# SCH_Elektrisch_Schema_B_2022-11-22.net
KiCad netlist of a schematic drawn in EasyEDA
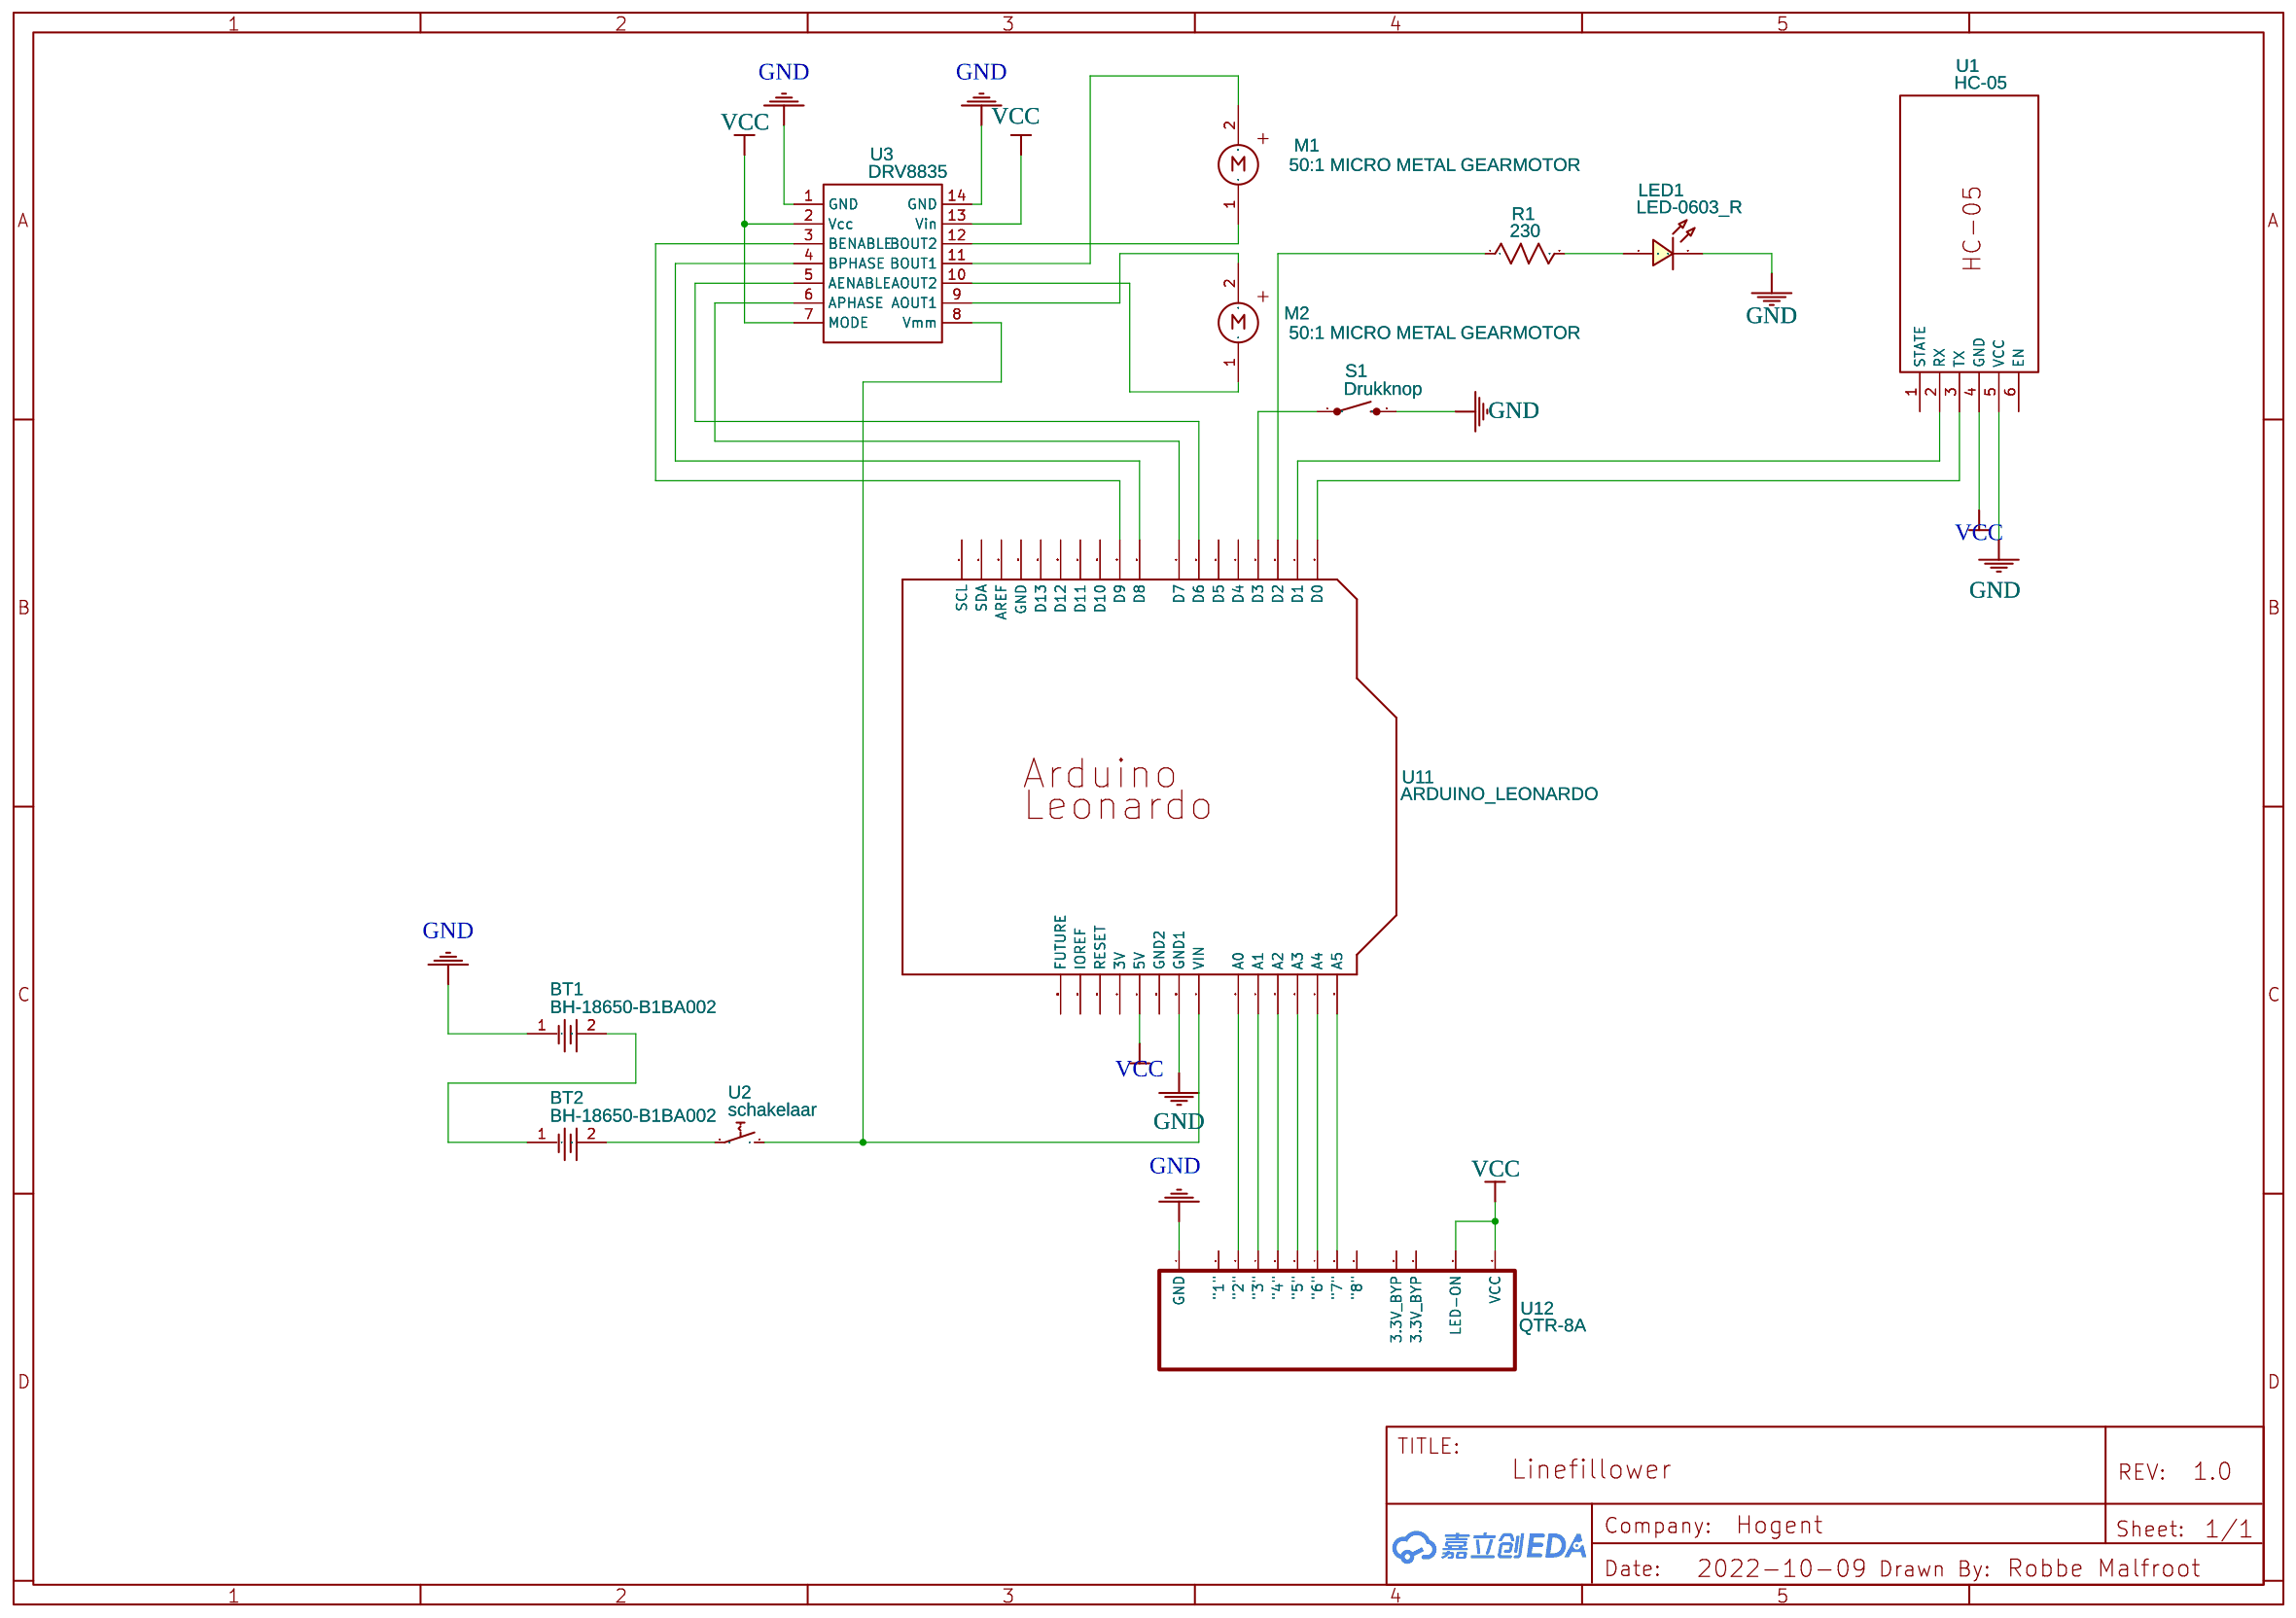
[diagram p0: Elektrisch schema B]
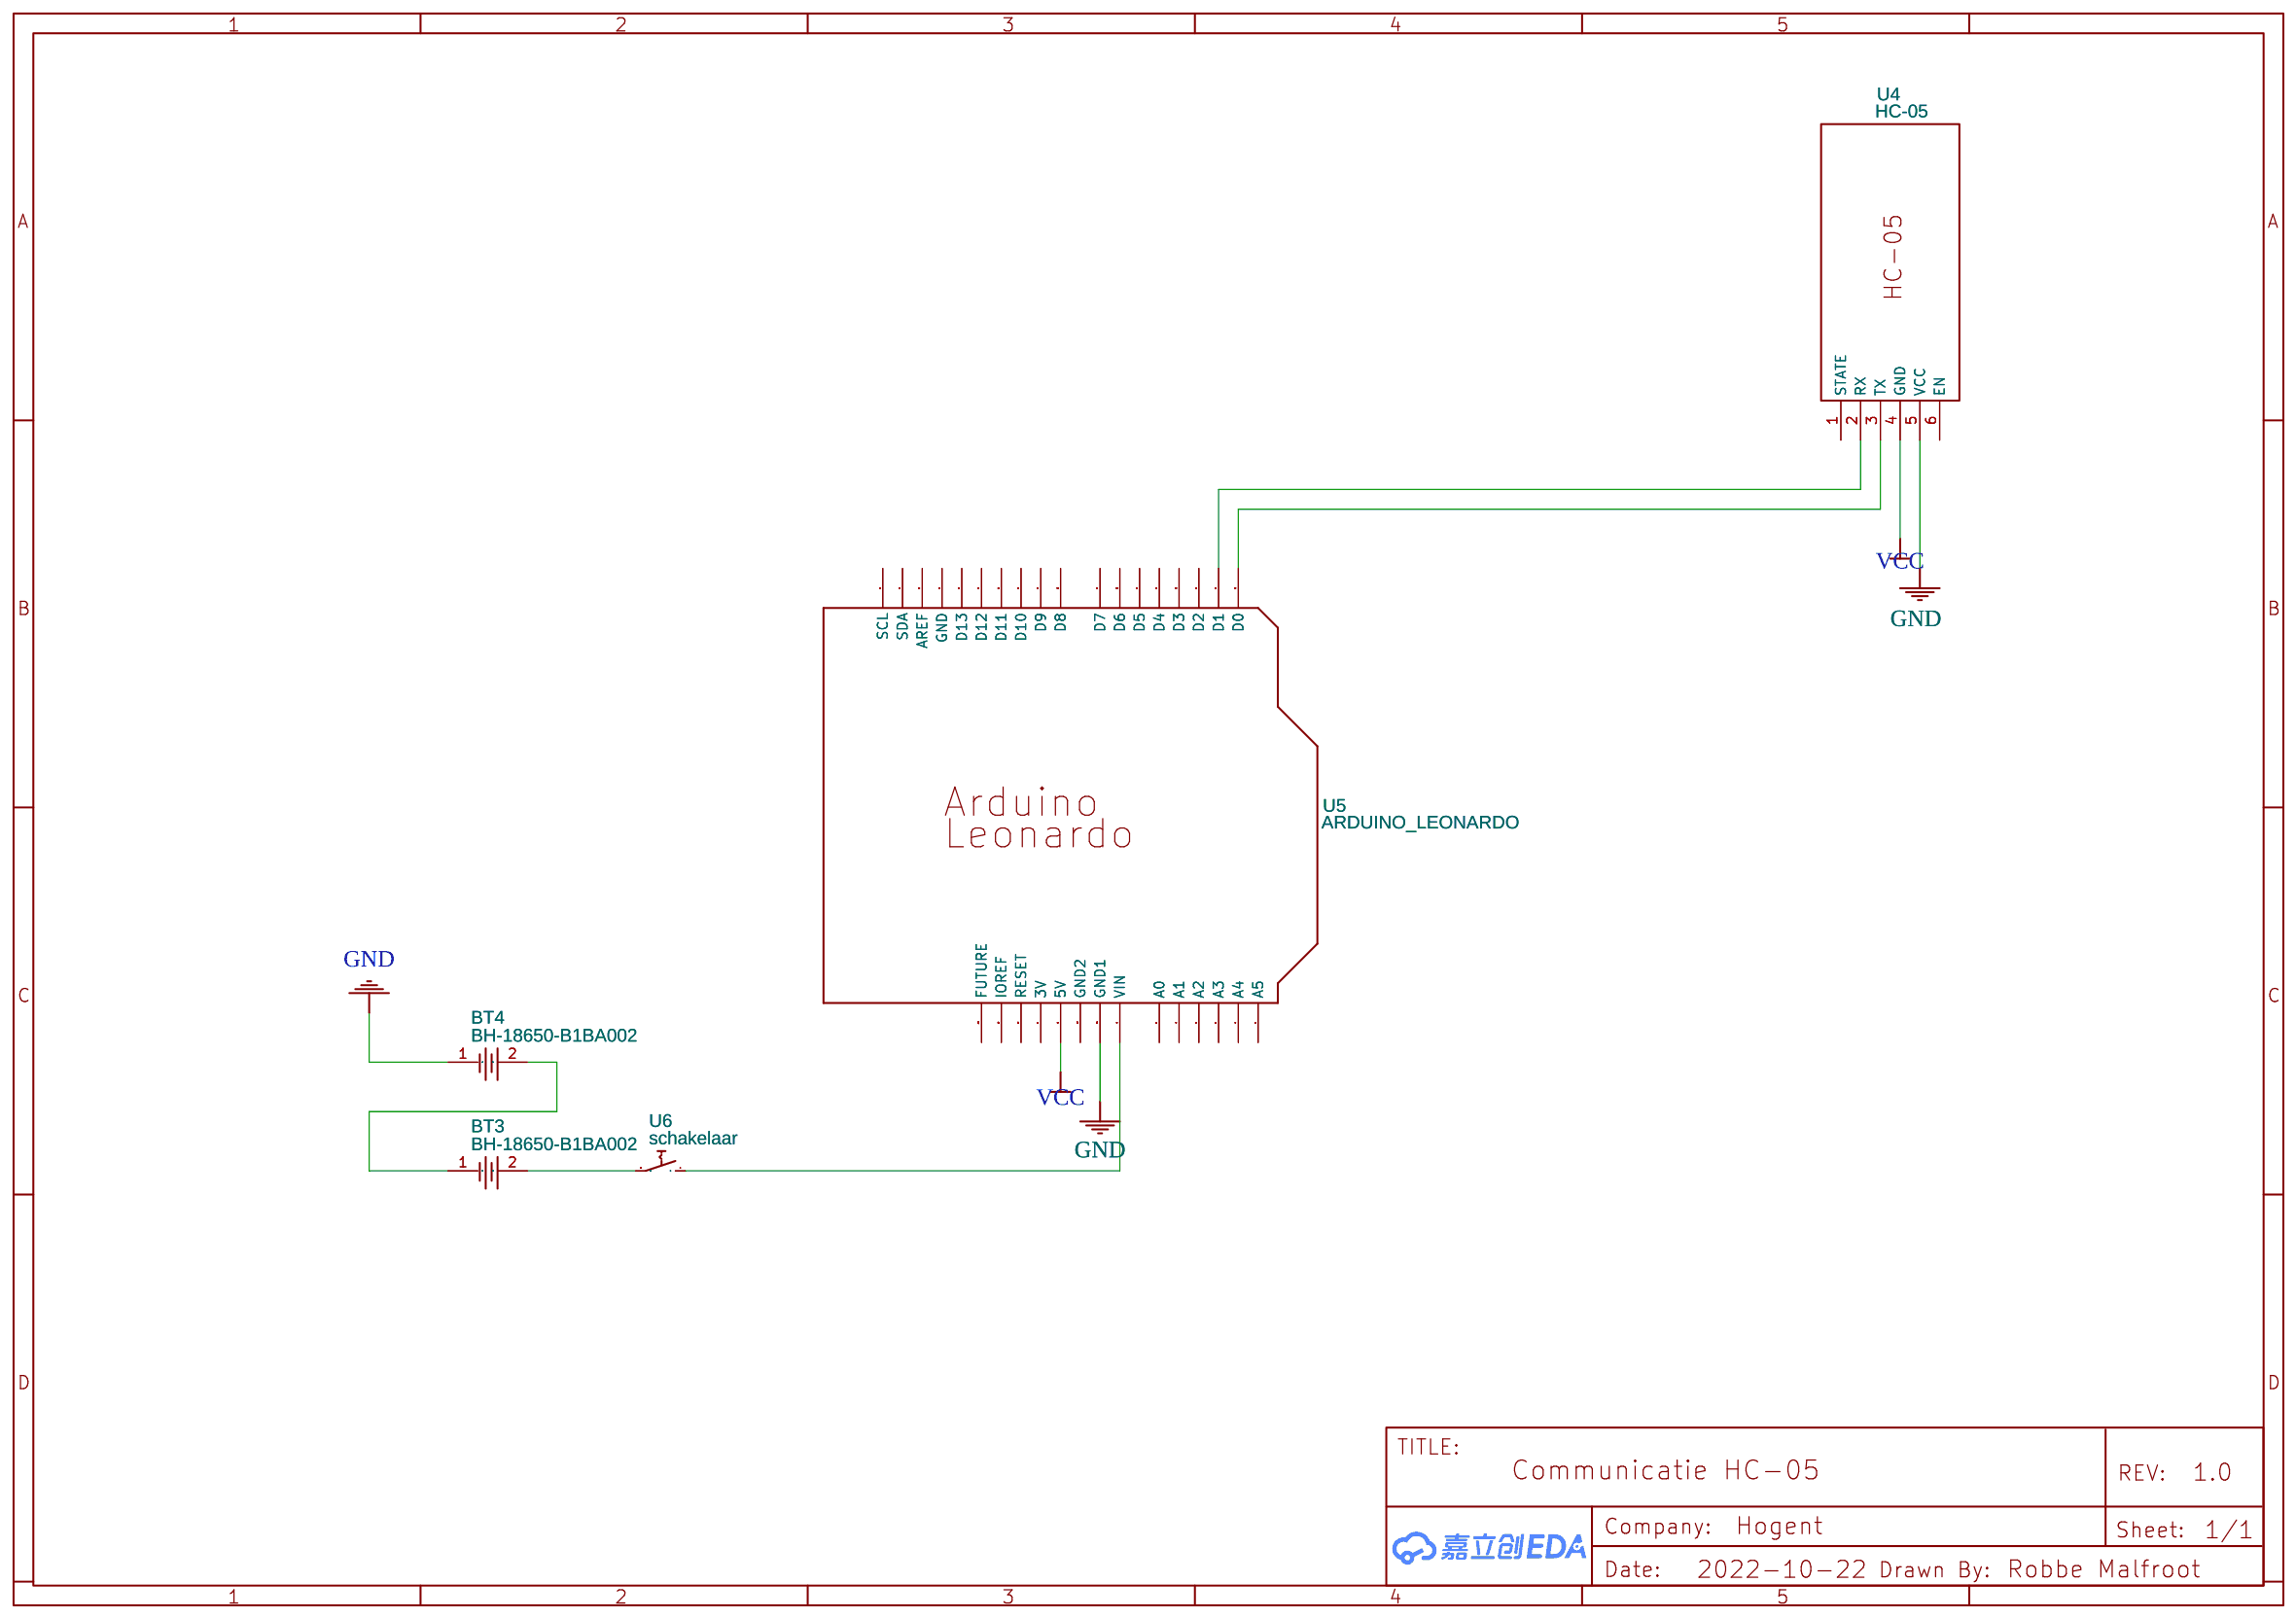
[diagram p1: Communicatie_HC-05]
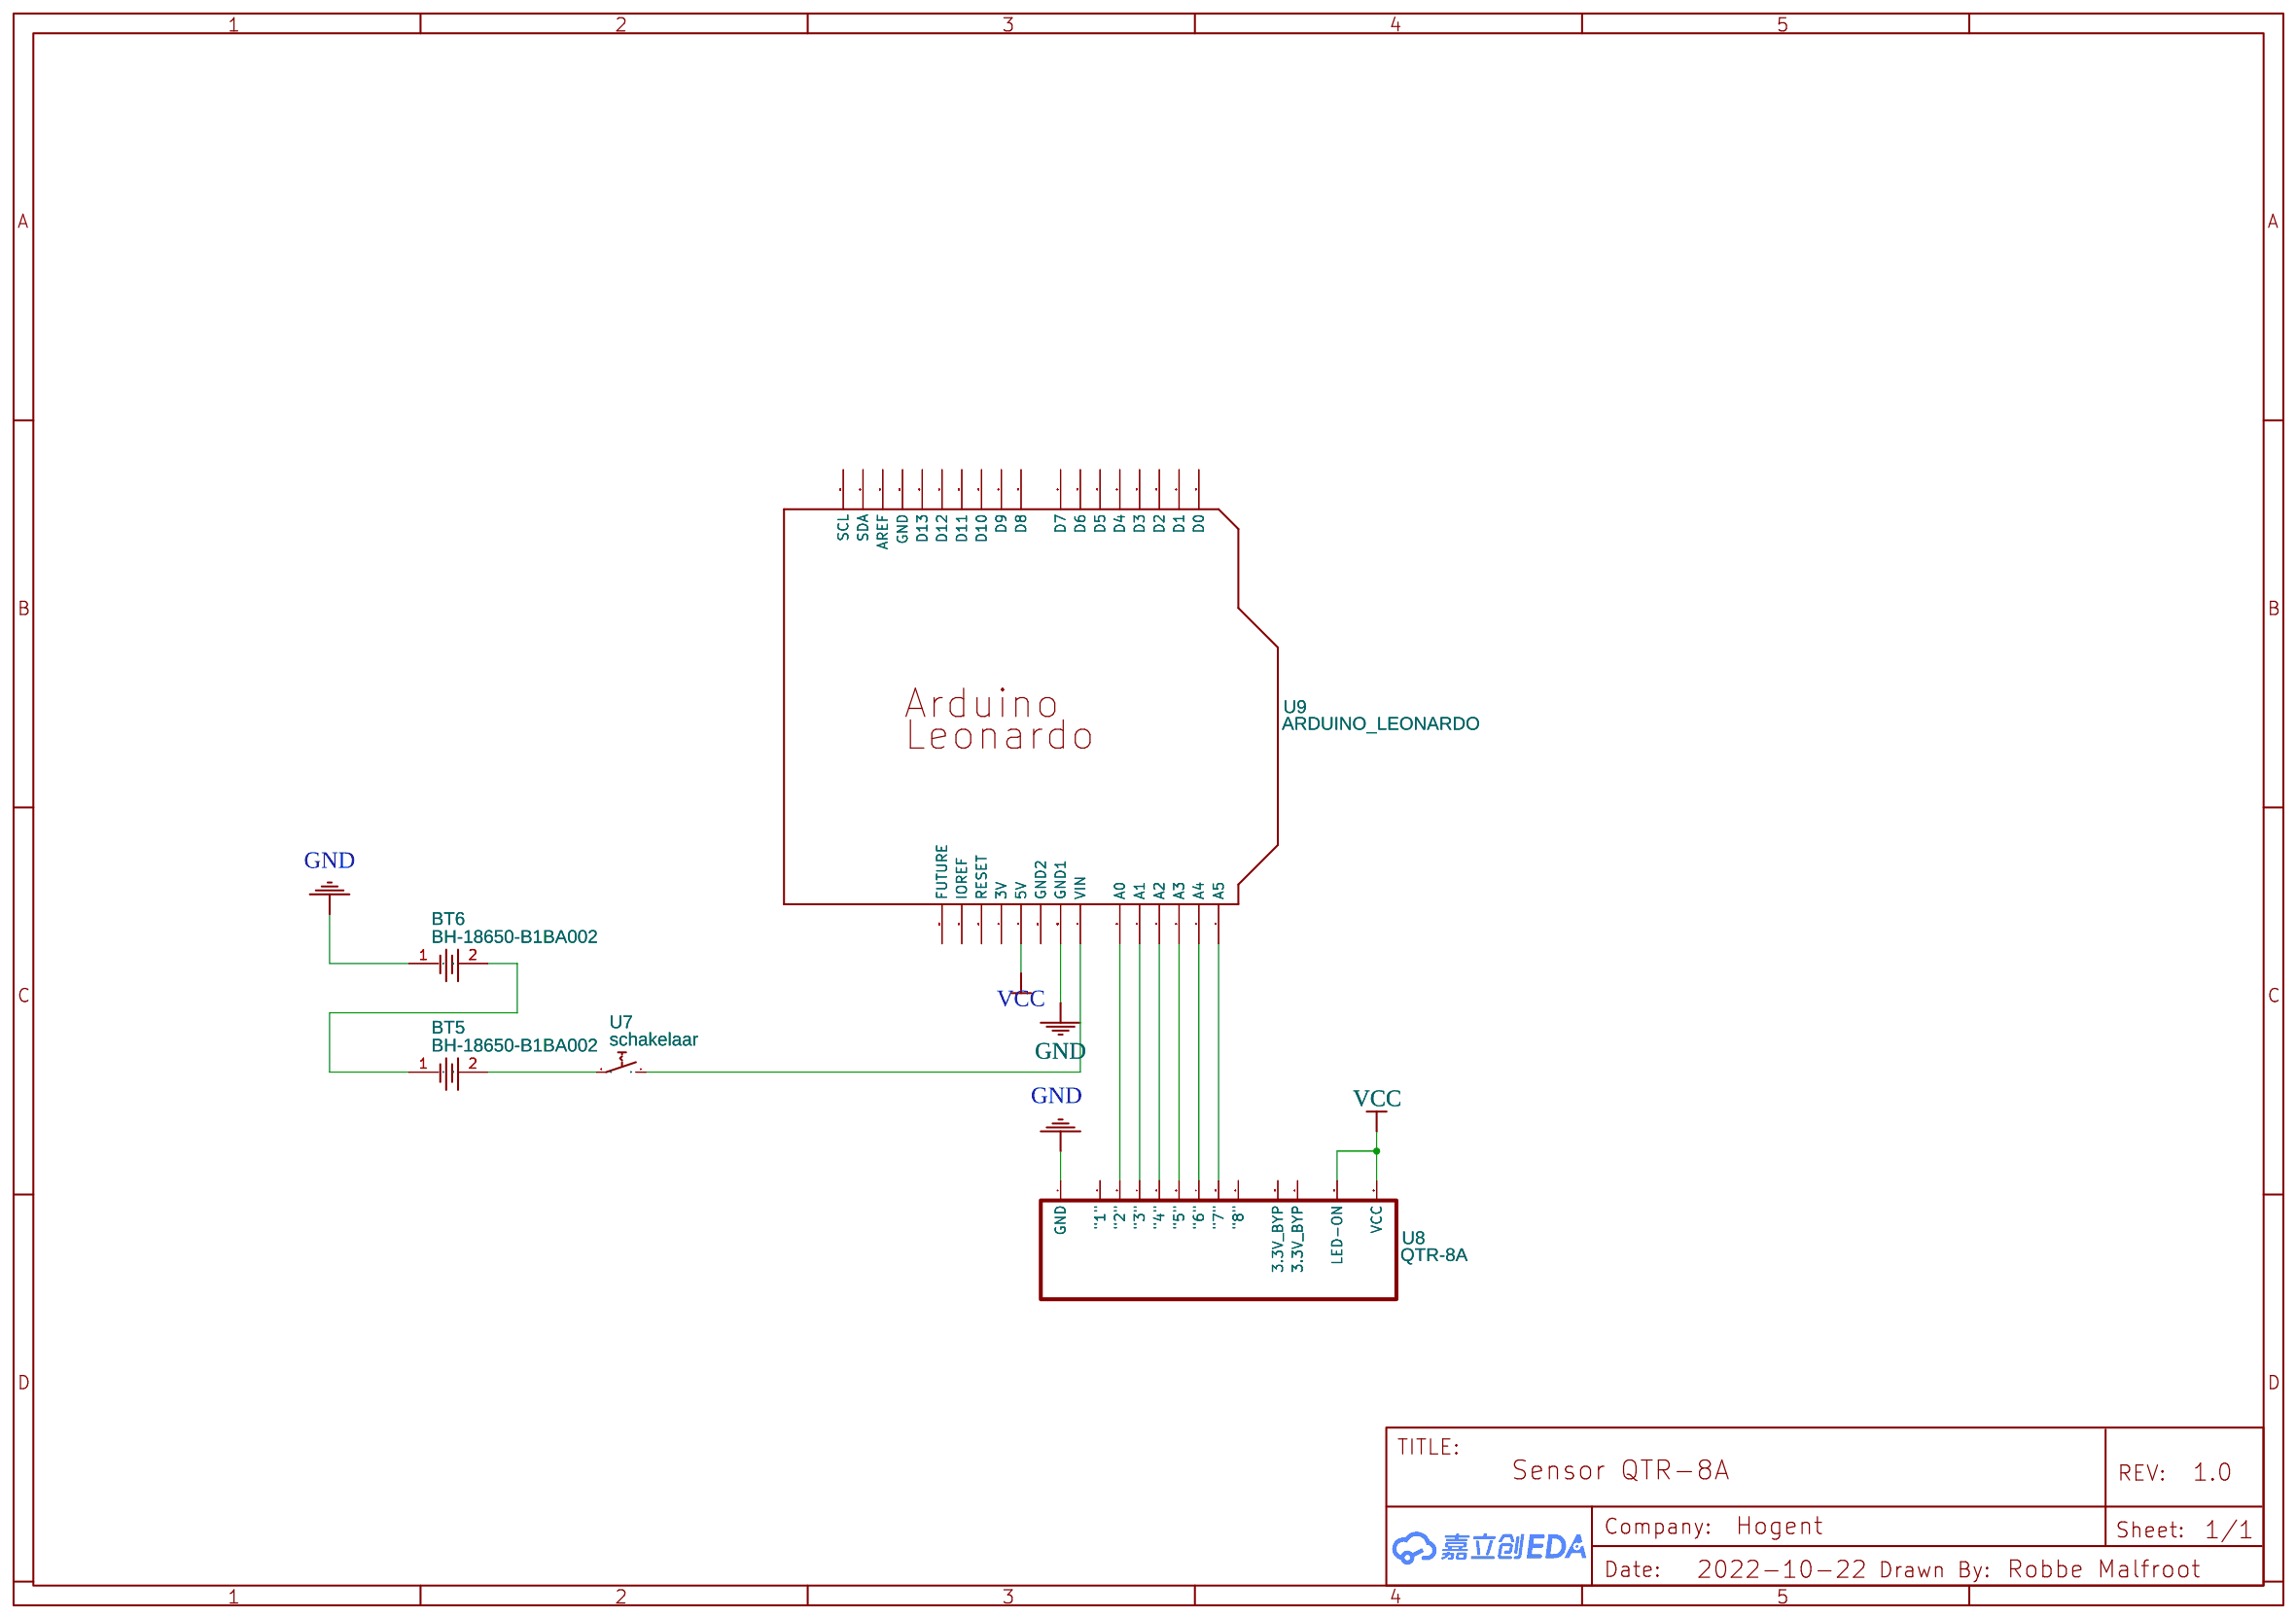
[diagram p2: QTR-8A]
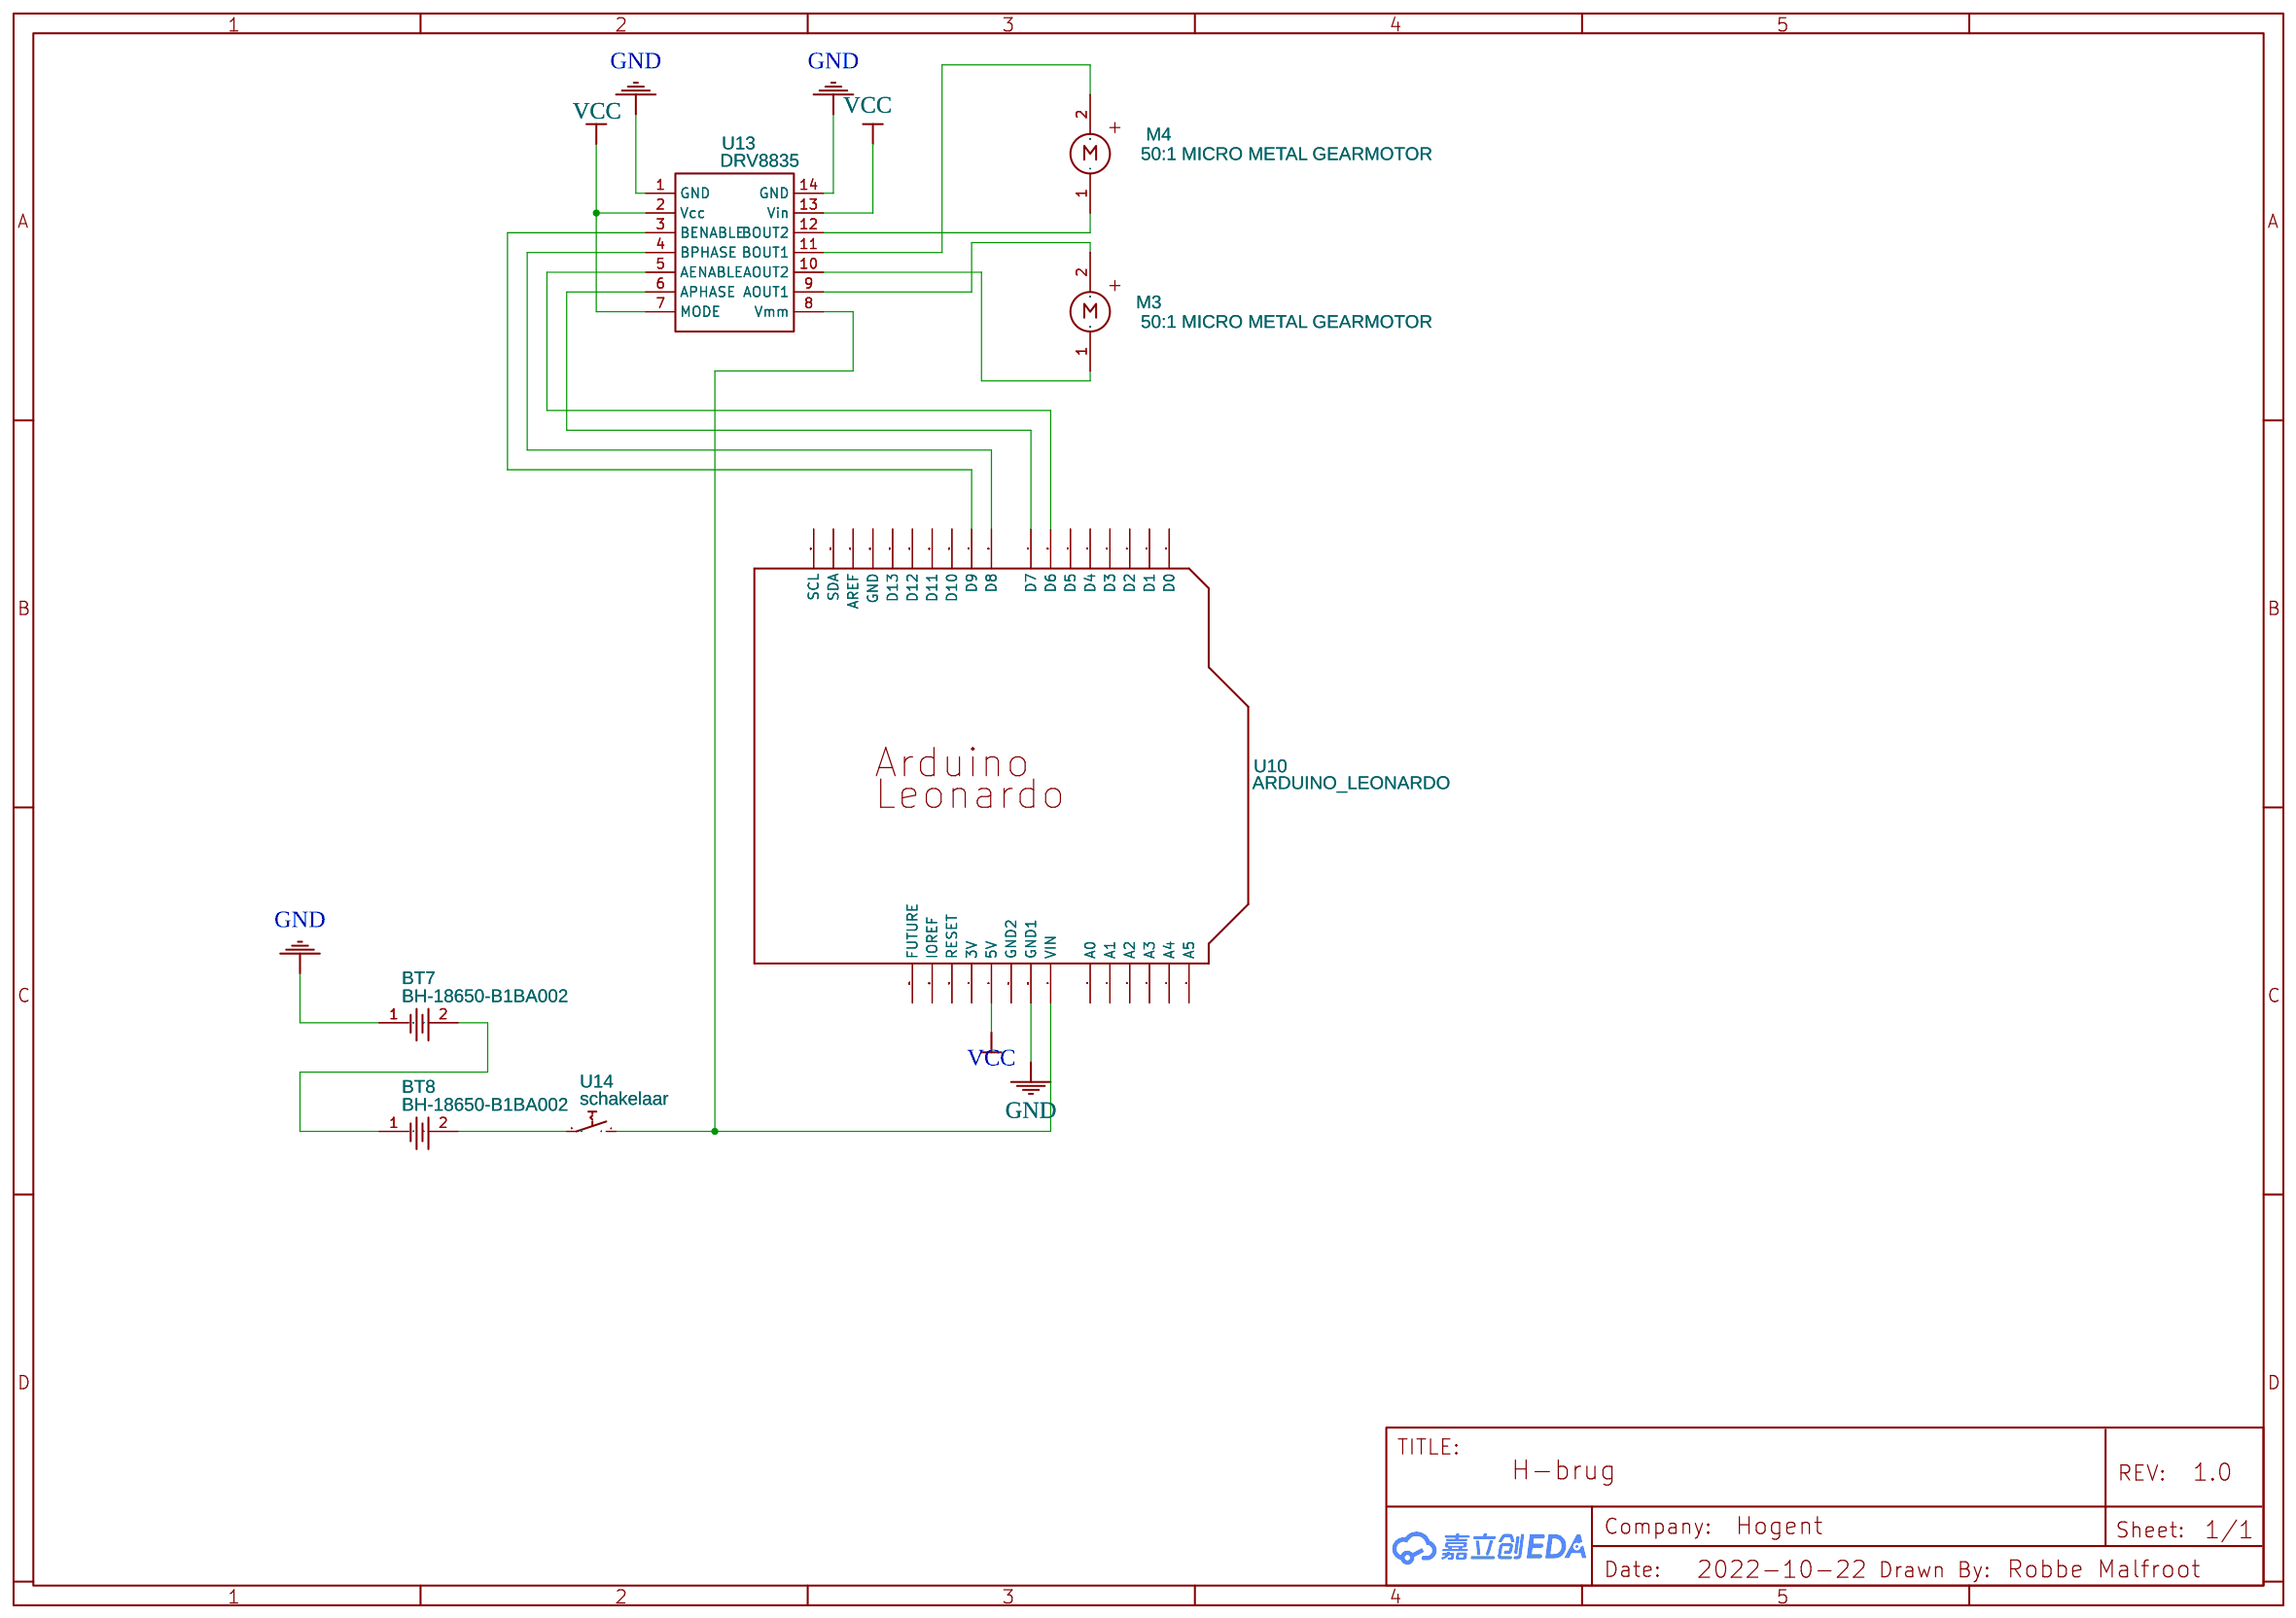
[diagram p3: H-brug DRV8835]

(export (version "E")
  (design (tool "Eeschema 10.0.6"))
  (components
    (comp (ref "BT1")
      (value "BH-18650-B1BA002")
      (fields (field (name "BOM_Supplier Part") "C2988620"))
      (libsource (lib "") (part "BH-18650-B1BA002"))
    )
    (comp (ref "BT2")
      (value "BH-18650-B1BA002")
      (fields (field (name "BOM_Supplier Part") "C2988620"))
      (libsource (lib "") (part "BH-18650-B1BA002"))
    )
    (comp (ref "LED1")
      (value "LED-0603_R")
      (fields
        (field (name "BOM_Manufacturer Part") "19-217/R6C-AL1M2VY/3T")
        (field (name "BOM_Supplier Part") "C72044")
      )
      (libsource (lib "") (part "LED-0603_R"))
    )
    (comp (ref "M1")
      (value "50:1 MICRO METAL GEARMOTOR")
      (fields
        (field (name "BOM_Manufacturer Part") "10:1 Micro Metal Gearmotor HPCB 6V with Extended Motor Shaft")
        (field (name "BOM_Supplier Part") "3071")
      )
      (libsource (lib "") (part "10{colon}1 MICRO METAL GEARMOTOR eskere"))
    )
    (comp (ref "M2")
      (value "50:1 MICRO METAL GEARMOTOR")
      (fields
        (field (name "BOM_Manufacturer Part") "10:1 Micro Metal Gearmotor HPCB 6V with Extended Motor Shaft")
        (field (name "BOM_Supplier Part") "3071")
      )
      (libsource (lib "") (part "10{colon}1 MICRO METAL GEARMOTOR eskere"))
    )
    (comp (ref "R1") (value "230") (libsource (lib "") (part "R_0603_US")))
    (comp (ref "S1") (value "Drukknop") (libsource (lib "") (part "Drukknop")))
    (comp (ref "U1") (value "HC-05") (libsource (lib "") (part "HM-10")))
    (comp (ref "U2") (value "schakelaar") (libsource (lib "") (part "schakelaar")))
    (comp (ref "U3") (value "DRV8835") (libsource (lib "") (part "DRV8835")))
    (comp (ref "U11") (value "ARDUINO_LEONARDO") (libsource (lib "") (part "ARDUINO_LEONARDO")))
    (comp (ref "U12")
      (value "QTR-8A")
      (fields (field (name "BOM_Supplier Part") "960"))
      (libsource (lib "") (part "QTR-8A"))
    )
    (comp (ref "BT3")
      (value "BH-18650-B1BA002")
      (fields (field (name "BOM_Supplier Part") "C2988620"))
      (libsource (lib "") (part "BH-18650-B1BA002"))
    )
    (comp (ref "BT4")
      (value "BH-18650-B1BA002")
      (fields (field (name "BOM_Supplier Part") "C2988620"))
      (libsource (lib "") (part "BH-18650-B1BA002"))
    )
    (comp (ref "U4") (value "HC-05") (libsource (lib "") (part "HM-10")))
    (comp (ref "U5") (value "ARDUINO_LEONARDO") (libsource (lib "") (part "ARDUINO_LEONARDO")))
    (comp (ref "U6") (value "schakelaar") (libsource (lib "") (part "schakelaar")))
    (comp (ref "BT5")
      (value "BH-18650-B1BA002")
      (fields (field (name "BOM_Supplier Part") "C2988620"))
      (libsource (lib "") (part "BH-18650-B1BA002"))
    )
    (comp (ref "BT6")
      (value "BH-18650-B1BA002")
      (fields (field (name "BOM_Supplier Part") "C2988620"))
      (libsource (lib "") (part "BH-18650-B1BA002"))
    )
    (comp (ref "U7") (value "schakelaar") (libsource (lib "") (part "schakelaar")))
    (comp (ref "U8")
      (value "QTR-8A")
      (fields (field (name "BOM_Supplier Part") "960"))
      (libsource (lib "") (part "QTR-8A"))
    )
    (comp (ref "U9") (value "ARDUINO_LEONARDO") (libsource (lib "") (part "ARDUINO_LEONARDO")))
    (comp (ref "BT7")
      (value "BH-18650-B1BA002")
      (fields (field (name "BOM_Supplier Part") "C2988620"))
      (libsource (lib "") (part "BH-18650-B1BA002"))
    )
    (comp (ref "BT8")
      (value "BH-18650-B1BA002")
      (fields (field (name "BOM_Supplier Part") "C2988620"))
      (libsource (lib "") (part "BH-18650-B1BA002"))
    )
    (comp (ref "M3")
      (value "50:1 MICRO METAL GEARMOTOR")
      (fields
        (field (name "BOM_Manufacturer Part") "10:1 Micro Metal Gearmotor HPCB 6V with Extended Motor Shaft")
        (field (name "BOM_Supplier Part") "3071")
      )
      (libsource (lib "") (part "10{colon}1 MICRO METAL GEARMOTOR eskere"))
    )
    (comp (ref "M4")
      (value "50:1 MICRO METAL GEARMOTOR")
      (fields
        (field (name "BOM_Manufacturer Part") "10:1 Micro Metal Gearmotor HPCB 6V with Extended Motor Shaft")
        (field (name "BOM_Supplier Part") "3071")
      )
      (libsource (lib "") (part "10{colon}1 MICRO METAL GEARMOTOR eskere"))
    )
    (comp (ref "U10") (value "ARDUINO_LEONARDO") (libsource (lib "") (part "ARDUINO_LEONARDO")))
    (comp (ref "U13") (value "DRV8835") (libsource (lib "") (part "DRV8835")))
    (comp (ref "U14") (value "schakelaar") (libsource (lib "") (part "schakelaar")))
  )
  (nets
    (net (code "1") (name "GND") (class "Default")
      (node (ref "BT1") (pin "1") (pinfunction "1_1") (pintype "input"))
      (node (ref "BT4") (pin "1") (pinfunction "1_1") (pintype "input"))
      (node (ref "BT6") (pin "1") (pinfunction "1_1") (pintype "input"))
      (node (ref "BT7") (pin "1") (pinfunction "1_1") (pintype "input"))
      (node (ref "LED1") (pin "2") (pinfunction "2_2") (pintype "unspecified"))
      (node (ref "S1") (pin "2") (pinfunction "2_2") (pintype "unspecified"))
      (node (ref "U1") (pin "5") (pinfunction "VCC_5") (pintype "unspecified"))
      (node (ref "U10") (pin "GND$3") (pinfunction "GND1_GND$3") (pintype "passive"))
      (node (ref "U11") (pin "GND$3") (pinfunction "GND1_GND$3") (pintype "passive"))
      (node (ref "U12") (pin "1") (pinfunction "GND_1") (pintype "unspecified"))
      (node (ref "U13") (pin "1") (pinfunction "GND_1") (pintype "unspecified"))
      (node (ref "U13") (pin "14") (pinfunction "GND_14") (pintype "unspecified"))
      (node (ref "U3") (pin "1") (pinfunction "GND_1") (pintype "unspecified"))
      (node (ref "U3") (pin "14") (pinfunction "GND_14") (pintype "unspecified"))
      (node (ref "U4") (pin "5") (pinfunction "VCC_5") (pintype "unspecified"))
      (node (ref "U5") (pin "GND$3") (pinfunction "GND1_GND$3") (pintype "passive"))
      (node (ref "U8") (pin "1") (pinfunction "GND_1") (pintype "unspecified"))
      (node (ref "U9") (pin "GND$3") (pinfunction "GND1_GND$3") (pintype "passive"))
    )
    (net (code "2") (name "Net-(BT1-Pad2)") (class "Default")
      (node (ref "BT1") (pin "2") (pinfunction "2_2") (pintype "input"))
      (node (ref "BT2") (pin "1") (pinfunction "1_1") (pintype "input"))
    )
    (net (code "3") (name "Net-(BT2-Pad2)") (class "Default")
      (node (ref "BT2") (pin "2") (pinfunction "2_2") (pintype "input"))
      (node (ref "U2") (pin "2") (pinfunction "2_2") (pintype "unspecified"))
    )
    (net (code "4") (name "Net-(BT3-Pad1)") (class "Default")
      (node (ref "BT3") (pin "1") (pinfunction "1_1") (pintype "input"))
      (node (ref "BT4") (pin "2") (pinfunction "2_2") (pintype "input"))
    )
    (net (code "5") (name "Net-(BT3-Pad2)") (class "Default")
      (node (ref "BT3") (pin "2") (pinfunction "2_2") (pintype "input"))
      (node (ref "U6") (pin "2") (pinfunction "2_2") (pintype "unspecified"))
    )
    (net (code "6") (name "Net-(BT5-Pad1)") (class "Default")
      (node (ref "BT5") (pin "1") (pinfunction "1_1") (pintype "input"))
      (node (ref "BT6") (pin "2") (pinfunction "2_2") (pintype "input"))
    )
    (net (code "7") (name "Net-(BT5-Pad2)") (class "Default")
      (node (ref "BT5") (pin "2") (pinfunction "2_2") (pintype "input"))
      (node (ref "U7") (pin "2") (pinfunction "2_2") (pintype "unspecified"))
    )
    (net (code "8") (name "Net-(BT7-Pad2)") (class "Default")
      (node (ref "BT7") (pin "2") (pinfunction "2_2") (pintype "input"))
      (node (ref "BT8") (pin "1") (pinfunction "1_1") (pintype "input"))
    )
    (net (code "9") (name "Net-(BT8-Pad2)") (class "Default")
      (node (ref "BT8") (pin "2") (pinfunction "2_2") (pintype "input"))
      (node (ref "U14") (pin "2") (pinfunction "2_2") (pintype "unspecified"))
    )
    (net (code "10") (name "Net-(LED1-Pad1)") (class "Default")
      (node (ref "LED1") (pin "1") (pinfunction "1_1") (pintype "unspecified"))
      (node (ref "R1") (pin "2") (pinfunction "2_2") (pintype "unspecified"))
    )
    (net (code "11") (name "Net-(R1-Pad1)") (class "Default")
      (node (ref "R1") (pin "1") (pinfunction "1_1") (pintype "unspecified"))
      (node (ref "U11") (pin "D2") (pinfunction "D2_D2") (pintype "unspecified"))
    )
    (net (code "12") (name "Net-(S1-Pad1)") (class "Default")
      (node (ref "S1") (pin "1") (pinfunction "1_1") (pintype "unspecified"))
      (node (ref "U11") (pin "D3") (pinfunction "D3_D3") (pintype "unspecified"))
    )
    (net (code "13") (name "Net-(U1-RX)") (class "Default")
      (node (ref "U1") (pin "2") (pinfunction "RX_2") (pintype "unspecified"))
      (node (ref "U11") (pin "D1") (pinfunction "D1_D1") (pintype "unspecified"))
    )
    (net (code "14") (name "Net-(U1-TX)") (class "Default")
      (node (ref "U1") (pin "3") (pinfunction "TX_3") (pintype "unspecified"))
      (node (ref "U11") (pin "D0") (pinfunction "D0_D0") (pintype "unspecified"))
    )
    (net (code "15") (name "Net-(U3-AENABLE)") (class "Default")
      (node (ref "U11") (pin "D6") (pinfunction "D6_D6") (pintype "unspecified"))
      (node (ref "U3") (pin "5") (pinfunction "AENABLE_5") (pintype "unspecified"))
    )
    (net (code "16") (name "Net-(U3-AOUT1)") (class "Default")
      (node (ref "M2") (pin "2") (pinfunction "2_2") (pintype "unspecified"))
      (node (ref "U3") (pin "9") (pinfunction "AOUT1_9") (pintype "unspecified"))
    )
    (net (code "17") (name "Net-(U3-AOUT2)") (class "Default")
      (node (ref "M2") (pin "1") (pinfunction "1_1") (pintype "unspecified"))
      (node (ref "U3") (pin "10") (pinfunction "AOUT2_10") (pintype "unspecified"))
    )
    (net (code "18") (name "Net-(U3-APHASE)") (class "Default")
      (node (ref "U11") (pin "D7") (pinfunction "D7_D7") (pintype "unspecified"))
      (node (ref "U3") (pin "6") (pinfunction "APHASE_6") (pintype "unspecified"))
    )
    (net (code "19") (name "Net-(U3-BENABLE)") (class "Default")
      (node (ref "U11") (pin "D9") (pinfunction "D9_D9") (pintype "unspecified"))
      (node (ref "U3") (pin "3") (pinfunction "BENABLE_3") (pintype "unspecified"))
    )
    (net (code "20") (name "Net-(U3-BOUT1)") (class "Default")
      (node (ref "M1") (pin "2") (pinfunction "2_2") (pintype "unspecified"))
      (node (ref "U3") (pin "11") (pinfunction "BOUT1_11") (pintype "unspecified"))
    )
    (net (code "21") (name "Net-(U3-BOUT2)") (class "Default")
      (node (ref "M1") (pin "1") (pinfunction "1_1") (pintype "unspecified"))
      (node (ref "U3") (pin "12") (pinfunction "BOUT2_12") (pintype "unspecified"))
    )
    (net (code "22") (name "Net-(U3-BPHASE)") (class "Default")
      (node (ref "U11") (pin "D8") (pinfunction "D8_D8") (pintype "unspecified"))
      (node (ref "U3") (pin "4") (pinfunction "BPHASE_4") (pintype "unspecified"))
    )
    (net (code "23") (name "Net-(U3-Vmm)") (class "Default")
      (node (ref "U11") (pin "VIN") (pinfunction "VIN_VIN") (pintype "passive"))
      (node (ref "U2") (pin "1") (pinfunction "1_1") (pintype "unspecified"))
      (node (ref "U3") (pin "8") (pinfunction "Vmm_8") (pintype "unspecified"))
    )
    (net (code "24") (name "Net-(U4-RX)") (class "Default")
      (node (ref "U4") (pin "2") (pinfunction "RX_2") (pintype "unspecified"))
      (node (ref "U5") (pin "D1") (pinfunction "D1_D1") (pintype "unspecified"))
    )
    (net (code "25") (name "Net-(U4-TX)") (class "Default")
      (node (ref "U4") (pin "3") (pinfunction "TX_3") (pintype "unspecified"))
      (node (ref "U5") (pin "D0") (pinfunction "D0_D0") (pintype "unspecified"))
    )
    (net (code "26") (name "Net-(U5-PadVIN)") (class "Default")
      (node (ref "U5") (pin "VIN") (pinfunction "VIN_VIN") (pintype "passive"))
      (node (ref "U6") (pin "1") (pinfunction "1_1") (pintype "unspecified"))
    )
    (net (code "27") (name "Net-(U7-Pad1)") (class "Default")
      (node (ref "U7") (pin "1") (pinfunction "1_1") (pintype "unspecified"))
      (node (ref "U9") (pin "VIN") (pinfunction "VIN_VIN") (pintype "passive"))
    )
    (net (code "28") (name "Net-(U8-\"2\")") (class "Default")
      (node (ref "U8") (pin "3") (pinfunction "\"2\"_3") (pintype "unspecified"))
      (node (ref "U9") (pin "A0") (pinfunction "A0_A0") (pintype "unspecified"))
    )
    (net (code "29") (name "Net-(U8-\"3\")") (class "Default")
      (node (ref "U8") (pin "4") (pinfunction "\"3\"_4") (pintype "unspecified"))
      (node (ref "U9") (pin "A1") (pinfunction "A1_A1") (pintype "unspecified"))
    )
    (net (code "30") (name "Net-(U8-\"4\")") (class "Default")
      (node (ref "U8") (pin "5") (pinfunction "\"4\"_5") (pintype "unspecified"))
      (node (ref "U9") (pin "A2") (pinfunction "A2_A2") (pintype "unspecified"))
    )
    (net (code "31") (name "Net-(U8-\"5\")") (class "Default")
      (node (ref "U8") (pin "6") (pinfunction "\"5\"_6") (pintype "unspecified"))
      (node (ref "U9") (pin "A3") (pinfunction "A3_A3") (pintype "unspecified"))
    )
    (net (code "32") (name "Net-(U8-\"6\")") (class "Default")
      (node (ref "U8") (pin "7") (pinfunction "\"6\"_7") (pintype "unspecified"))
      (node (ref "U9") (pin "A4") (pinfunction "A4_A4") (pintype "unspecified"))
    )
    (net (code "33") (name "Net-(U8-\"7\")") (class "Default")
      (node (ref "U8") (pin "8") (pinfunction "\"7\"_8") (pintype "unspecified"))
      (node (ref "U9") (pin "A5") (pinfunction "A5_A5") (pintype "unspecified"))
    )
    (net (code "34") (name "Net-(U12-\"2\")") (class "Default")
      (node (ref "U11") (pin "A0") (pinfunction "A0_A0") (pintype "unspecified"))
      (node (ref "U12") (pin "3") (pinfunction "\"2\"_3") (pintype "unspecified"))
    )
    (net (code "35") (name "Net-(U12-\"3\")") (class "Default")
      (node (ref "U11") (pin "A1") (pinfunction "A1_A1") (pintype "unspecified"))
      (node (ref "U12") (pin "4") (pinfunction "\"3\"_4") (pintype "unspecified"))
    )
    (net (code "36") (name "Net-(U12-\"4\")") (class "Default")
      (node (ref "U11") (pin "A2") (pinfunction "A2_A2") (pintype "unspecified"))
      (node (ref "U12") (pin "5") (pinfunction "\"4\"_5") (pintype "unspecified"))
    )
    (net (code "37") (name "Net-(U12-\"5\")") (class "Default")
      (node (ref "U11") (pin "A3") (pinfunction "A3_A3") (pintype "unspecified"))
      (node (ref "U12") (pin "6") (pinfunction "\"5\"_6") (pintype "unspecified"))
    )
    (net (code "38") (name "Net-(U12-\"6\")") (class "Default")
      (node (ref "U11") (pin "A4") (pinfunction "A4_A4") (pintype "unspecified"))
      (node (ref "U12") (pin "7") (pinfunction "\"6\"_7") (pintype "unspecified"))
    )
    (net (code "39") (name "Net-(U12-\"7\")") (class "Default")
      (node (ref "U11") (pin "A5") (pinfunction "A5_A5") (pintype "unspecified"))
      (node (ref "U12") (pin "8") (pinfunction "\"7\"_8") (pintype "unspecified"))
    )
    (net (code "40") (name "Net-(U13-AENABLE)") (class "Default")
      (node (ref "U10") (pin "D6") (pinfunction "D6_D6") (pintype "unspecified"))
      (node (ref "U13") (pin "5") (pinfunction "AENABLE_5") (pintype "unspecified"))
    )
    (net (code "41") (name "Net-(U13-AOUT1)") (class "Default")
      (node (ref "M3") (pin "2") (pinfunction "2_2") (pintype "unspecified"))
      (node (ref "U13") (pin "9") (pinfunction "AOUT1_9") (pintype "unspecified"))
    )
    (net (code "42") (name "Net-(U13-AOUT2)") (class "Default")
      (node (ref "M3") (pin "1") (pinfunction "1_1") (pintype "unspecified"))
      (node (ref "U13") (pin "10") (pinfunction "AOUT2_10") (pintype "unspecified"))
    )
    (net (code "43") (name "Net-(U13-APHASE)") (class "Default")
      (node (ref "U10") (pin "D7") (pinfunction "D7_D7") (pintype "unspecified"))
      (node (ref "U13") (pin "6") (pinfunction "APHASE_6") (pintype "unspecified"))
    )
    (net (code "44") (name "Net-(U13-BENABLE)") (class "Default")
      (node (ref "U10") (pin "D9") (pinfunction "D9_D9") (pintype "unspecified"))
      (node (ref "U13") (pin "3") (pinfunction "BENABLE_3") (pintype "unspecified"))
    )
    (net (code "45") (name "Net-(U13-BOUT1)") (class "Default")
      (node (ref "M4") (pin "2") (pinfunction "2_2") (pintype "unspecified"))
      (node (ref "U13") (pin "11") (pinfunction "BOUT1_11") (pintype "unspecified"))
    )
    (net (code "46") (name "Net-(U13-BOUT2)") (class "Default")
      (node (ref "M4") (pin "1") (pinfunction "1_1") (pintype "unspecified"))
      (node (ref "U13") (pin "12") (pinfunction "BOUT2_12") (pintype "unspecified"))
    )
    (net (code "47") (name "Net-(U13-BPHASE)") (class "Default")
      (node (ref "U10") (pin "D8") (pinfunction "D8_D8") (pintype "unspecified"))
      (node (ref "U13") (pin "4") (pinfunction "BPHASE_4") (pintype "unspecified"))
    )
    (net (code "48") (name "Net-(U13-Vmm)") (class "Default")
      (node (ref "U10") (pin "VIN") (pinfunction "VIN_VIN") (pintype "passive"))
      (node (ref "U13") (pin "8") (pinfunction "Vmm_8") (pintype "unspecified"))
      (node (ref "U14") (pin "1") (pinfunction "1_1") (pintype "unspecified"))
    )
    (net (code "49") (name "VCC") (class "Default")
      (node (ref "U1") (pin "4") (pinfunction "GND_4") (pintype "unspecified"))
      (node (ref "U10") (pin "5V") (pinfunction "5V_5V") (pintype "passive"))
      (node (ref "U11") (pin "5V") (pinfunction "5V_5V") (pintype "passive"))
      (node (ref "U12") (pin "12") (pinfunction "VCC_12") (pintype "unspecified"))
      (node (ref "U13") (pin "13") (pinfunction "Vin_13") (pintype "unspecified"))
      (node (ref "U13") (pin "2") (pinfunction "Vcc_2") (pintype "unspecified"))
      (node (ref "U13") (pin "7") (pinfunction "MODE_7") (pintype "unspecified"))
      (node (ref "U3") (pin "13") (pinfunction "Vin_13") (pintype "unspecified"))
      (node (ref "U3") (pin "2") (pinfunction "Vcc_2") (pintype "unspecified"))
      (node (ref "U3") (pin "7") (pinfunction "MODE_7") (pintype "unspecified"))
      (node (ref "U4") (pin "4") (pinfunction "GND_4") (pintype "unspecified"))
      (node (ref "U5") (pin "5V") (pinfunction "5V_5V") (pintype "passive"))
      (node (ref "U8") (pin "12") (pinfunction "LED-ON_12") (pintype "unspecified"))
      (node (ref "U9") (pin "5V") (pinfunction "5V_5V") (pintype "passive"))
    )
    (net (code "50") (name "unconnected-(U1-EN-Pad6)") (class "Default")
      (node (ref "U1") (pin "6") (pinfunction "EN_6") (pintype "unspecified"))
    )
    (net (code "51") (name "unconnected-(U1-STATE-Pad1)") (class "Default")
      (node (ref "U1") (pin "1") (pinfunction "STATE_1") (pintype "unspecified"))
    )
    (net (code "52") (name "unconnected-(U4-EN-Pad6)") (class "Default")
      (node (ref "U4") (pin "6") (pinfunction "EN_6") (pintype "unspecified"))
    )
    (net (code "53") (name "unconnected-(U4-STATE-Pad1)") (class "Default")
      (node (ref "U4") (pin "1") (pinfunction "STATE_1") (pintype "unspecified"))
    )
    (net (code "54") (name "unconnected-(U5-FUTURE-PadRESERVED)") (class "Default")
      (node (ref "U5") (pin "RESERVED") (pinfunction "FUTURE_RESERVED") (pintype "unspecified"))
    )
    (net (code "55") (name "unconnected-(U5-GND2-PadGND$2)") (class "Default")
      (node (ref "U5") (pin "GND$2") (pinfunction "GND2_GND$2") (pintype "passive"))
    )
    (net (code "56") (name "unconnected-(U5-Pad3V)") (class "Default")
      (node (ref "U5") (pin "3V") (pinfunction "3V_3V") (pintype "passive"))
    )
    (net (code "57") (name "unconnected-(U5-PadA0)") (class "Default")
      (node (ref "U5") (pin "A0") (pinfunction "A0_A0") (pintype "unspecified"))
    )
    (net (code "58") (name "unconnected-(U5-PadA1)") (class "Default")
      (node (ref "U5") (pin "A1") (pinfunction "A1_A1") (pintype "unspecified"))
    )
    (net (code "59") (name "unconnected-(U5-PadA2)") (class "Default")
      (node (ref "U5") (pin "A2") (pinfunction "A2_A2") (pintype "unspecified"))
    )
    (net (code "60") (name "unconnected-(U5-PadA3)") (class "Default")
      (node (ref "U5") (pin "A3") (pinfunction "A3_A3") (pintype "unspecified"))
    )
    (net (code "61") (name "unconnected-(U5-PadA4)") (class "Default")
      (node (ref "U5") (pin "A4") (pinfunction "A4_A4") (pintype "unspecified"))
    )
    (net (code "62") (name "unconnected-(U5-PadA5)") (class "Default")
      (node (ref "U5") (pin "A5") (pinfunction "A5_A5") (pintype "unspecified"))
    )
    (net (code "63") (name "unconnected-(U5-PadAREF)") (class "Default")
      (node (ref "U5") (pin "AREF") (pinfunction "AREF_AREF") (pintype "unspecified"))
    )
    (net (code "64") (name "unconnected-(U5-PadD2)") (class "Default")
      (node (ref "U5") (pin "D2") (pinfunction "D2_D2") (pintype "unspecified"))
    )
    (net (code "65") (name "unconnected-(U5-PadD3)") (class "Default")
      (node (ref "U5") (pin "D3") (pinfunction "D3_D3") (pintype "unspecified"))
    )
    (net (code "66") (name "unconnected-(U5-PadD4)") (class "Default")
      (node (ref "U5") (pin "D4") (pinfunction "D4_D4") (pintype "unspecified"))
    )
    (net (code "67") (name "unconnected-(U5-PadD5)") (class "Default")
      (node (ref "U5") (pin "D5") (pinfunction "D5_D5") (pintype "unspecified"))
    )
    (net (code "68") (name "unconnected-(U5-PadD6)") (class "Default")
      (node (ref "U5") (pin "D6") (pinfunction "D6_D6") (pintype "unspecified"))
    )
    (net (code "69") (name "unconnected-(U5-PadD7)") (class "Default")
      (node (ref "U5") (pin "D7") (pinfunction "D7_D7") (pintype "unspecified"))
    )
    (net (code "70") (name "unconnected-(U5-PadD8)") (class "Default")
      (node (ref "U5") (pin "D8") (pinfunction "D8_D8") (pintype "unspecified"))
    )
    (net (code "71") (name "unconnected-(U5-PadD9)") (class "Default")
      (node (ref "U5") (pin "D9") (pinfunction "D9_D9") (pintype "unspecified"))
    )
    (net (code "72") (name "unconnected-(U5-PadD10)") (class "Default")
      (node (ref "U5") (pin "D10") (pinfunction "D10_D10") (pintype "unspecified"))
    )
    (net (code "73") (name "unconnected-(U5-PadD11)") (class "Default")
      (node (ref "U5") (pin "D11") (pinfunction "D11_D11") (pintype "unspecified"))
    )
    (net (code "74") (name "unconnected-(U5-PadD12)") (class "Default")
      (node (ref "U5") (pin "D12") (pinfunction "D12_D12") (pintype "unspecified"))
    )
    (net (code "75") (name "unconnected-(U5-PadD13)") (class "Default")
      (node (ref "U5") (pin "D13") (pinfunction "D13_D13") (pintype "unspecified"))
    )
    (net (code "76") (name "unconnected-(U5-PadGND)") (class "Default")
      (node (ref "U5") (pin "GND") (pinfunction "GND_GND") (pintype "passive"))
    )
    (net (code "77") (name "unconnected-(U5-PadIOREF)") (class "Default")
      (node (ref "U5") (pin "IOREF") (pinfunction "IOREF_IOREF") (pintype "unspecified"))
    )
    (net (code "78") (name "unconnected-(U5-PadRESET)") (class "Default")
      (node (ref "U5") (pin "RESET") (pinfunction "RESET_RESET") (pintype "unspecified"))
    )
    (net (code "79") (name "unconnected-(U5-PadSCL)") (class "Default")
      (node (ref "U5") (pin "SCL") (pinfunction "SCL_SCL") (pintype "unspecified"))
    )
    (net (code "80") (name "unconnected-(U5-PadSDA)") (class "Default")
      (node (ref "U5") (pin "SDA") (pinfunction "SDA_SDA") (pintype "unspecified"))
    )
    (net (code "81") (name "unconnected-(U8-\"1\"-Pad2)") (class "Default")
      (node (ref "U8") (pin "2") (pinfunction "\"1\"_2") (pintype "unspecified"))
    )
    (net (code "82") (name "unconnected-(U8-\"8\"-Pad9)") (class "Default")
      (node (ref "U8") (pin "9") (pinfunction "\"8\"_9") (pintype "unspecified"))
    )
    (net (code "83") (name "unconnected-(U8-3.3V_BYP-Pad10)") (class "Default")
      (node (ref "U8") (pin "10") (pinfunction "3.3V_BYP_10") (pintype "unspecified"))
    )
    (net (code "84") (name "unconnected-(U8-3.3V_BYP-Pad11)") (class "Default")
      (node (ref "U8") (pin "11") (pinfunction "3.3V_BYP_11") (pintype "unspecified"))
    )
    (net (code "85") (name "unconnected-(U9-FUTURE-PadRESERVED)") (class "Default")
      (node (ref "U9") (pin "RESERVED") (pinfunction "FUTURE_RESERVED") (pintype "unspecified"))
    )
    (net (code "86") (name "unconnected-(U9-GND2-PadGND$2)") (class "Default")
      (node (ref "U9") (pin "GND$2") (pinfunction "GND2_GND$2") (pintype "passive"))
    )
    (net (code "87") (name "unconnected-(U9-Pad3V)") (class "Default")
      (node (ref "U9") (pin "3V") (pinfunction "3V_3V") (pintype "passive"))
    )
    (net (code "88") (name "unconnected-(U9-PadAREF)") (class "Default")
      (node (ref "U9") (pin "AREF") (pinfunction "AREF_AREF") (pintype "unspecified"))
    )
    (net (code "89") (name "unconnected-(U9-PadD0)") (class "Default")
      (node (ref "U9") (pin "D0") (pinfunction "D0_D0") (pintype "unspecified"))
    )
    (net (code "90") (name "unconnected-(U9-PadD1)") (class "Default")
      (node (ref "U9") (pin "D1") (pinfunction "D1_D1") (pintype "unspecified"))
    )
    (net (code "91") (name "unconnected-(U9-PadD2)") (class "Default")
      (node (ref "U9") (pin "D2") (pinfunction "D2_D2") (pintype "unspecified"))
    )
    (net (code "92") (name "unconnected-(U9-PadD3)") (class "Default")
      (node (ref "U9") (pin "D3") (pinfunction "D3_D3") (pintype "unspecified"))
    )
    (net (code "93") (name "unconnected-(U9-PadD4)") (class "Default")
      (node (ref "U9") (pin "D4") (pinfunction "D4_D4") (pintype "unspecified"))
    )
    (net (code "94") (name "unconnected-(U9-PadD5)") (class "Default")
      (node (ref "U9") (pin "D5") (pinfunction "D5_D5") (pintype "unspecified"))
    )
    (net (code "95") (name "unconnected-(U9-PadD6)") (class "Default")
      (node (ref "U9") (pin "D6") (pinfunction "D6_D6") (pintype "unspecified"))
    )
    (net (code "96") (name "unconnected-(U9-PadD7)") (class "Default")
      (node (ref "U9") (pin "D7") (pinfunction "D7_D7") (pintype "unspecified"))
    )
    (net (code "97") (name "unconnected-(U9-PadD8)") (class "Default")
      (node (ref "U9") (pin "D8") (pinfunction "D8_D8") (pintype "unspecified"))
    )
    (net (code "98") (name "unconnected-(U9-PadD9)") (class "Default")
      (node (ref "U9") (pin "D9") (pinfunction "D9_D9") (pintype "unspecified"))
    )
    (net (code "99") (name "unconnected-(U9-PadD10)") (class "Default")
      (node (ref "U9") (pin "D10") (pinfunction "D10_D10") (pintype "unspecified"))
    )
    (net (code "100") (name "unconnected-(U9-PadD11)") (class "Default")
      (node (ref "U9") (pin "D11") (pinfunction "D11_D11") (pintype "unspecified"))
    )
    (net (code "101") (name "unconnected-(U9-PadD12)") (class "Default")
      (node (ref "U9") (pin "D12") (pinfunction "D12_D12") (pintype "unspecified"))
    )
    (net (code "102") (name "unconnected-(U9-PadD13)") (class "Default")
      (node (ref "U9") (pin "D13") (pinfunction "D13_D13") (pintype "unspecified"))
    )
    (net (code "103") (name "unconnected-(U9-PadGND)") (class "Default")
      (node (ref "U9") (pin "GND") (pinfunction "GND_GND") (pintype "passive"))
    )
    (net (code "104") (name "unconnected-(U9-PadIOREF)") (class "Default")
      (node (ref "U9") (pin "IOREF") (pinfunction "IOREF_IOREF") (pintype "unspecified"))
    )
    (net (code "105") (name "unconnected-(U9-PadRESET)") (class "Default")
      (node (ref "U9") (pin "RESET") (pinfunction "RESET_RESET") (pintype "unspecified"))
    )
    (net (code "106") (name "unconnected-(U9-PadSCL)") (class "Default")
      (node (ref "U9") (pin "SCL") (pinfunction "SCL_SCL") (pintype "unspecified"))
    )
    (net (code "107") (name "unconnected-(U9-PadSDA)") (class "Default")
      (node (ref "U9") (pin "SDA") (pinfunction "SDA_SDA") (pintype "unspecified"))
    )
    (net (code "108") (name "unconnected-(U10-FUTURE-PadRESERVED)") (class "Default")
      (node (ref "U10") (pin "RESERVED") (pinfunction "FUTURE_RESERVED") (pintype "unspecified"))
    )
    (net (code "109") (name "unconnected-(U10-GND2-PadGND$2)") (class "Default")
      (node (ref "U10") (pin "GND$2") (pinfunction "GND2_GND$2") (pintype "passive"))
    )
    (net (code "110") (name "unconnected-(U10-Pad3V)") (class "Default")
      (node (ref "U10") (pin "3V") (pinfunction "3V_3V") (pintype "passive"))
    )
    (net (code "111") (name "unconnected-(U10-PadA0)") (class "Default")
      (node (ref "U10") (pin "A0") (pinfunction "A0_A0") (pintype "unspecified"))
    )
    (net (code "112") (name "unconnected-(U10-PadA1)") (class "Default")
      (node (ref "U10") (pin "A1") (pinfunction "A1_A1") (pintype "unspecified"))
    )
    (net (code "113") (name "unconnected-(U10-PadA2)") (class "Default")
      (node (ref "U10") (pin "A2") (pinfunction "A2_A2") (pintype "unspecified"))
    )
    (net (code "114") (name "unconnected-(U10-PadA3)") (class "Default")
      (node (ref "U10") (pin "A3") (pinfunction "A3_A3") (pintype "unspecified"))
    )
    (net (code "115") (name "unconnected-(U10-PadA4)") (class "Default")
      (node (ref "U10") (pin "A4") (pinfunction "A4_A4") (pintype "unspecified"))
    )
    (net (code "116") (name "unconnected-(U10-PadA5)") (class "Default")
      (node (ref "U10") (pin "A5") (pinfunction "A5_A5") (pintype "unspecified"))
    )
    (net (code "117") (name "unconnected-(U10-PadAREF)") (class "Default")
      (node (ref "U10") (pin "AREF") (pinfunction "AREF_AREF") (pintype "unspecified"))
    )
    (net (code "118") (name "unconnected-(U10-PadD0)") (class "Default")
      (node (ref "U10") (pin "D0") (pinfunction "D0_D0") (pintype "unspecified"))
    )
    (net (code "119") (name "unconnected-(U10-PadD1)") (class "Default")
      (node (ref "U10") (pin "D1") (pinfunction "D1_D1") (pintype "unspecified"))
    )
    (net (code "120") (name "unconnected-(U10-PadD2)") (class "Default")
      (node (ref "U10") (pin "D2") (pinfunction "D2_D2") (pintype "unspecified"))
    )
    (net (code "121") (name "unconnected-(U10-PadD3)") (class "Default")
      (node (ref "U10") (pin "D3") (pinfunction "D3_D3") (pintype "unspecified"))
    )
    (net (code "122") (name "unconnected-(U10-PadD4)") (class "Default")
      (node (ref "U10") (pin "D4") (pinfunction "D4_D4") (pintype "unspecified"))
    )
    (net (code "123") (name "unconnected-(U10-PadD5)") (class "Default")
      (node (ref "U10") (pin "D5") (pinfunction "D5_D5") (pintype "unspecified"))
    )
    (net (code "124") (name "unconnected-(U10-PadD10)") (class "Default")
      (node (ref "U10") (pin "D10") (pinfunction "D10_D10") (pintype "unspecified"))
    )
    (net (code "125") (name "unconnected-(U10-PadD11)") (class "Default")
      (node (ref "U10") (pin "D11") (pinfunction "D11_D11") (pintype "unspecified"))
    )
    (net (code "126") (name "unconnected-(U10-PadD12)") (class "Default")
      (node (ref "U10") (pin "D12") (pinfunction "D12_D12") (pintype "unspecified"))
    )
    (net (code "127") (name "unconnected-(U10-PadD13)") (class "Default")
      (node (ref "U10") (pin "D13") (pinfunction "D13_D13") (pintype "unspecified"))
    )
    (net (code "128") (name "unconnected-(U10-PadGND)") (class "Default")
      (node (ref "U10") (pin "GND") (pinfunction "GND_GND") (pintype "passive"))
    )
    (net (code "129") (name "unconnected-(U10-PadIOREF)") (class "Default")
      (node (ref "U10") (pin "IOREF") (pinfunction "IOREF_IOREF") (pintype "unspecified"))
    )
    (net (code "130") (name "unconnected-(U10-PadRESET)") (class "Default")
      (node (ref "U10") (pin "RESET") (pinfunction "RESET_RESET") (pintype "unspecified"))
    )
    (net (code "131") (name "unconnected-(U10-PadSCL)") (class "Default")
      (node (ref "U10") (pin "SCL") (pinfunction "SCL_SCL") (pintype "unspecified"))
    )
    (net (code "132") (name "unconnected-(U10-PadSDA)") (class "Default")
      (node (ref "U10") (pin "SDA") (pinfunction "SDA_SDA") (pintype "unspecified"))
    )
    (net (code "133") (name "unconnected-(U11-FUTURE-PadRESERVED)") (class "Default")
      (node (ref "U11") (pin "RESERVED") (pinfunction "FUTURE_RESERVED") (pintype "unspecified"))
    )
    (net (code "134") (name "unconnected-(U11-GND2-PadGND$2)") (class "Default")
      (node (ref "U11") (pin "GND$2") (pinfunction "GND2_GND$2") (pintype "passive"))
    )
    (net (code "135") (name "unconnected-(U11-Pad3V)") (class "Default")
      (node (ref "U11") (pin "3V") (pinfunction "3V_3V") (pintype "passive"))
    )
    (net (code "136") (name "unconnected-(U11-PadAREF)") (class "Default")
      (node (ref "U11") (pin "AREF") (pinfunction "AREF_AREF") (pintype "unspecified"))
    )
    (net (code "137") (name "unconnected-(U11-PadD4)") (class "Default")
      (node (ref "U11") (pin "D4") (pinfunction "D4_D4") (pintype "unspecified"))
    )
    (net (code "138") (name "unconnected-(U11-PadD5)") (class "Default")
      (node (ref "U11") (pin "D5") (pinfunction "D5_D5") (pintype "unspecified"))
    )
    (net (code "139") (name "unconnected-(U11-PadD10)") (class "Default")
      (node (ref "U11") (pin "D10") (pinfunction "D10_D10") (pintype "unspecified"))
    )
    (net (code "140") (name "unconnected-(U11-PadD11)") (class "Default")
      (node (ref "U11") (pin "D11") (pinfunction "D11_D11") (pintype "unspecified"))
    )
    (net (code "141") (name "unconnected-(U11-PadD12)") (class "Default")
      (node (ref "U11") (pin "D12") (pinfunction "D12_D12") (pintype "unspecified"))
    )
    (net (code "142") (name "unconnected-(U11-PadD13)") (class "Default")
      (node (ref "U11") (pin "D13") (pinfunction "D13_D13") (pintype "unspecified"))
    )
    (net (code "143") (name "unconnected-(U11-PadGND)") (class "Default")
      (node (ref "U11") (pin "GND") (pinfunction "GND_GND") (pintype "passive"))
    )
    (net (code "144") (name "unconnected-(U11-PadIOREF)") (class "Default")
      (node (ref "U11") (pin "IOREF") (pinfunction "IOREF_IOREF") (pintype "unspecified"))
    )
    (net (code "145") (name "unconnected-(U11-PadRESET)") (class "Default")
      (node (ref "U11") (pin "RESET") (pinfunction "RESET_RESET") (pintype "unspecified"))
    )
    (net (code "146") (name "unconnected-(U11-PadSCL)") (class "Default")
      (node (ref "U11") (pin "SCL") (pinfunction "SCL_SCL") (pintype "unspecified"))
    )
    (net (code "147") (name "unconnected-(U11-PadSDA)") (class "Default")
      (node (ref "U11") (pin "SDA") (pinfunction "SDA_SDA") (pintype "unspecified"))
    )
    (net (code "148") (name "unconnected-(U12-\"1\"-Pad2)") (class "Default")
      (node (ref "U12") (pin "2") (pinfunction "\"1\"_2") (pintype "unspecified"))
    )
    (net (code "149") (name "unconnected-(U12-\"8\"-Pad9)") (class "Default")
      (node (ref "U12") (pin "9") (pinfunction "\"8\"_9") (pintype "unspecified"))
    )
    (net (code "150") (name "unconnected-(U12-3.3V_BYP-Pad10)") (class "Default")
      (node (ref "U12") (pin "10") (pinfunction "3.3V_BYP_10") (pintype "unspecified"))
    )
    (net (code "151") (name "unconnected-(U12-3.3V_BYP-Pad11)") (class "Default")
      (node (ref "U12") (pin "11") (pinfunction "3.3V_BYP_11") (pintype "unspecified"))
    )
  )
)
